# deel3.net
KiCad netlist of a schematic drawn in Altium Designer
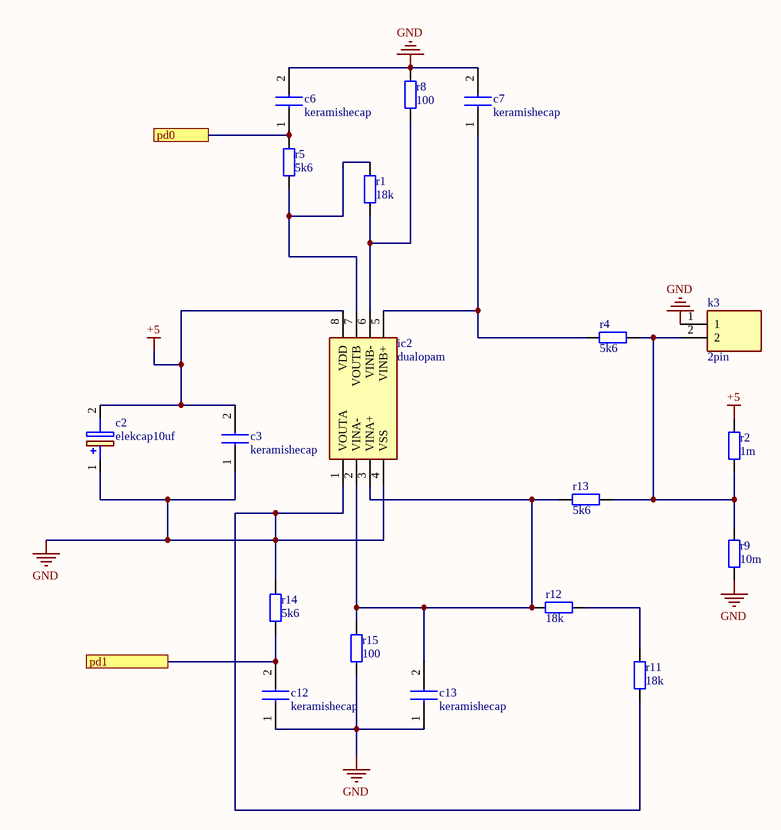
[diagram p0: deel3.SchDoc]

(export (version "E")
  (design (tool "Eeschema 10.0.6"))
  (components
    (comp (ref "c2")
      (value "elekcap10uf")
      (footprint "elekcap10uf")
      (description "Capacitor Polarised")
      (fields
        (field (name "MOUSER2 PART NUMBER") "667-EEU-FR1H100")
        (field (name "MANUFACTURER_PART_NUMBER") "EEU-FR1H100")
      )
      (libsource (lib "Schlib1") (part "elekcap10uf"))
    )
    (comp (ref "c3")
      (value "keramishecap")
      (footprint "0805")
      (description "Capacitor")
      (fields (field (name "MANUFACTURER_PART_NUMBER") "C1206C104K3GACAUTO"))
      (libsource (lib "Schlib1") (part "keramishecap"))
    )
    (comp (ref "c6")
      (value "keramishecap")
      (footprint "0805")
      (description "Capacitor")
      (fields (field (name "MANUFACTURER_PART_NUMBER") "C1206C104K3GACAUTO"))
      (libsource (lib "Schlib1") (part "keramishecap"))
    )
    (comp (ref "c7")
      (value "keramishecap")
      (footprint "0805")
      (description "Capacitor")
      (fields (field (name "MANUFACTURER_PART_NUMBER") "C1206C104K3GACAUTO"))
      (libsource (lib "Schlib1") (part "keramishecap"))
    )
    (comp (ref "c12")
      (value "keramishecap")
      (footprint "0805")
      (description "Capacitor")
      (fields (field (name "MANUFACTURER_PART_NUMBER") "C1206C104K3GACAUTO"))
      (libsource (lib "Schlib1") (part "keramishecap"))
    )
    (comp (ref "c13")
      (value "keramishecap")
      (footprint "0805")
      (description "Capacitor")
      (fields (field (name "MANUFACTURER_PART_NUMBER") "C1206C104K3GACAUTO"))
      (libsource (lib "Schlib1") (part "keramishecap"))
    )
    (comp (ref "ic2")
      (value "dualopam")
      (footprint "dualopam")
      (description "Integrated Circuit")
      (fields
        (field (name "MOUSER2 PART NUMBER") "579-MCP6002-E/P")
        (field (name "MANUFACTURER_PART_NUMBER") "MCP6002-E/P")
      )
      (libsource (lib "Schlib1") (part "dualopam"))
    )
    (comp (ref "k3")
      (value "2pin")
      (footprint "2pin")
      (description "Connector")
      (fields (field (name "MANUFACTURER_PART_NUMBER") "10129378-902001BLF"))
      (libsource (lib "Schlib1") (part "2pin"))
    )
    (comp (ref "r1")
      (value "18k")
      (footprint "0805")
      (description "WRIS-PSMB SMT Metal Plate Resistor, size 0805, 5mOhm, 0.5W")
      (fields
        (field (name "MANUFACTURER") "Wurth Elektronik")
        (field (name "MANUFACTURER PART NUMBER") "580060720003")
      )
      (libsource (lib "Schlib1") (part "weerstand0805"))
    )
    (comp (ref "r2")
      (value "1m")
      (footprint "0805")
      (description "WRIS-PSMB SMT Metal Plate Resistor, size 0805, 5mOhm, 0.5W")
      (fields
        (field (name "MANUFACTURER") "Wurth Elektronik")
        (field (name "MANUFACTURER PART NUMBER") "580060720003")
      )
      (libsource (lib "Schlib1") (part "weerstand0805"))
    )
    (comp (ref "r4")
      (value "5k6")
      (footprint "0805")
      (description "WRIS-PSMB SMT Metal Plate Resistor, size 0805, 5mOhm, 0.5W")
      (fields
        (field (name "MANUFACTURER") "Wurth Elektronik")
        (field (name "MANUFACTURER PART NUMBER") "580060720003")
      )
      (libsource (lib "") (part "weerstand0805_2"))
    )
    (comp (ref "r5")
      (value "5k6")
      (footprint "0805")
      (description "WRIS-PSMB SMT Metal Plate Resistor, size 0805, 5mOhm, 0.5W")
      (fields
        (field (name "MANUFACTURER") "Wurth Elektronik")
        (field (name "MANUFACTURER PART NUMBER") "580060720003")
      )
      (libsource (lib "") (part "weerstand0805_1"))
    )
    (comp (ref "r8")
      (value "100")
      (footprint "0805")
      (description "WRIS-PSMB SMT Metal Plate Resistor, size 0805, 5mOhm, 0.5W")
      (fields
        (field (name "MANUFACTURER") "Wurth Elektronik")
        (field (name "MANUFACTURER PART NUMBER") "580060720003")
      )
      (libsource (lib "Schlib1") (part "weerstand0805"))
    )
    (comp (ref "r9")
      (value "10m")
      (footprint "0805")
      (description "WRIS-PSMB SMT Metal Plate Resistor, size 0805, 5mOhm, 0.5W")
      (fields
        (field (name "MANUFACTURER") "Wurth Elektronik")
        (field (name "MANUFACTURER PART NUMBER") "580060720003")
      )
      (libsource (lib "Schlib1") (part "weerstand0805"))
    )
    (comp (ref "r11")
      (value "18k")
      (footprint "0805")
      (description "WRIS-PSMB SMT Metal Plate Resistor, size 0805, 5mOhm, 0.5W")
      (fields
        (field (name "MANUFACTURER") "Wurth Elektronik")
        (field (name "MANUFACTURER PART NUMBER") "580060720003")
      )
      (libsource (lib "Schlib1") (part "weerstand0805"))
    )
    (comp (ref "r12")
      (value "18k")
      (footprint "0805")
      (description "WRIS-PSMB SMT Metal Plate Resistor, size 0805, 5mOhm, 0.5W")
      (fields
        (field (name "MANUFACTURER") "Wurth Elektronik")
        (field (name "MANUFACTURER PART NUMBER") "580060720003")
      )
      (libsource (lib "") (part "weerstand0805_2"))
    )
    (comp (ref "r13")
      (value "5k6")
      (footprint "0805")
      (description "WRIS-PSMB SMT Metal Plate Resistor, size 0805, 5mOhm, 0.5W")
      (fields
        (field (name "MANUFACTURER") "Wurth Elektronik")
        (field (name "MANUFACTURER PART NUMBER") "580060720003")
      )
      (libsource (lib "") (part "weerstand0805_2"))
    )
    (comp (ref "r14")
      (value "5k6")
      (footprint "0805")
      (description "WRIS-PSMB SMT Metal Plate Resistor, size 0805, 5mOhm, 0.5W")
      (fields
        (field (name "MANUFACTURER") "Wurth Elektronik")
        (field (name "MANUFACTURER PART NUMBER") "580060720003")
      )
      (libsource (lib "Schlib1") (part "weerstand0805"))
    )
    (comp (ref "r15")
      (value "100")
      (footprint "0805")
      (description "WRIS-PSMB SMT Metal Plate Resistor, size 0805, 5mOhm, 0.5W")
      (fields
        (field (name "MANUFACTURER") "Wurth Elektronik")
        (field (name "MANUFACTURER PART NUMBER") "580060720003")
      )
      (libsource (lib "Schlib1") (part "weerstand0805"))
    )
  )
  (nets
    (net (code "1") (name "+5") (class "Default")
      (node (ref "c2") (pin "2") (pinfunction "-_2") (pintype "power_in"))
      (node (ref "c3") (pin "2") (pinfunction "2_2") (pintype "passive"))
      (node (ref "ic2") (pin "8") (pinfunction "VDD_8") (pintype "passive"))
      (node (ref "r2") (pin "2") (pinfunction "2_2") (pintype "passive"))
    )
    (net (code "2") (name "/pd0") (class "Default")
      (node (ref "c6") (pin "1") (pinfunction "1_1") (pintype "passive"))
      (node (ref "r5") (pin "1") (pinfunction "1_1") (pintype "passive"))
    )
    (net (code "3") (name "/pd1") (class "Default")
      (node (ref "c12") (pin "2") (pinfunction "2_2") (pintype "passive"))
      (node (ref "r14") (pin "1") (pinfunction "1_1") (pintype "passive"))
    )
    (net (code "4") (name "GND") (class "Default")
      (node (ref "c12") (pin "1") (pinfunction "1_1") (pintype "passive"))
      (node (ref "c13") (pin "1") (pinfunction "1_1") (pintype "passive"))
      (node (ref "c2") (pin "1") (pinfunction "+_1") (pintype "power_in"))
      (node (ref "c3") (pin "1") (pinfunction "1_1") (pintype "passive"))
      (node (ref "c6") (pin "2") (pinfunction "2_2") (pintype "passive"))
      (node (ref "c7") (pin "2") (pinfunction "2_2") (pintype "passive"))
      (node (ref "ic2") (pin "1") (pinfunction "VOUTA_1") (pintype "passive"))
      (node (ref "ic2") (pin "4") (pinfunction "VSS_4") (pintype "passive"))
      (node (ref "k3") (pin "1") (pinfunction "1_1") (pintype "passive"))
      (node (ref "r11") (pin "1") (pinfunction "1_1") (pintype "passive"))
      (node (ref "r14") (pin "2") (pinfunction "2_2") (pintype "passive"))
      (node (ref "r15") (pin "1") (pinfunction "1_1") (pintype "passive"))
      (node (ref "r8") (pin "2") (pinfunction "2_2") (pintype "passive"))
      (node (ref "r9") (pin "1") (pinfunction "1_1") (pintype "passive"))
    )
    (net (code "5") (name "Net-(ic2-VINA+)") (class "Default")
      (node (ref "c13") (pin "2") (pinfunction "2_2") (pintype "passive"))
      (node (ref "ic2") (pin "2") (pinfunction "VINA-_2") (pintype "passive"))
      (node (ref "ic2") (pin "3") (pinfunction "VINA+_3") (pintype "passive"))
      (node (ref "r12") (pin "1") (pinfunction "1_1") (pintype "passive"))
      (node (ref "r13") (pin "1") (pinfunction "1_1") (pintype "passive"))
      (node (ref "r15") (pin "2") (pinfunction "2_2") (pintype "passive"))
    )
    (net (code "6") (name "Net-(ic2-VINB+)") (class "Default")
      (node (ref "c7") (pin "1") (pinfunction "1_1") (pintype "passive"))
      (node (ref "ic2") (pin "5") (pinfunction "VINB+_5") (pintype "passive"))
      (node (ref "r4") (pin "1") (pinfunction "1_1") (pintype "passive"))
    )
    (net (code "7") (name "Net-(ic2-VINB-)") (class "Default")
      (node (ref "ic2") (pin "6") (pinfunction "VINB-_6") (pintype "passive"))
      (node (ref "r1") (pin "1") (pinfunction "1_1") (pintype "passive"))
      (node (ref "r8") (pin "1") (pinfunction "1_1") (pintype "passive"))
    )
    (net (code "8") (name "Net-(ic2-VOUTB)") (class "Default")
      (node (ref "ic2") (pin "7") (pinfunction "VOUTB_7") (pintype "passive"))
      (node (ref "r1") (pin "2") (pinfunction "2_2") (pintype "passive"))
      (node (ref "r5") (pin "2") (pinfunction "2_2") (pintype "passive"))
    )
    (net (code "9") (name "Net-(k3-Pad2)") (class "Default")
      (node (ref "k3") (pin "2") (pinfunction "2_2") (pintype "passive"))
      (node (ref "r13") (pin "2") (pinfunction "2_2") (pintype "passive"))
      (node (ref "r2") (pin "1") (pinfunction "1_1") (pintype "passive"))
      (node (ref "r4") (pin "2") (pinfunction "2_2") (pintype "passive"))
      (node (ref "r9") (pin "2") (pinfunction "2_2") (pintype "passive"))
    )
    (net (code "10") (name "Net-(r11-Pad2)") (class "Default")
      (node (ref "r11") (pin "2") (pinfunction "2_2") (pintype "passive"))
      (node (ref "r12") (pin "2") (pinfunction "2_2") (pintype "passive"))
    )
  )
)
